# TLE5012_S2G1.net
KiCad netlist of a schematic drawn in Altium Designer
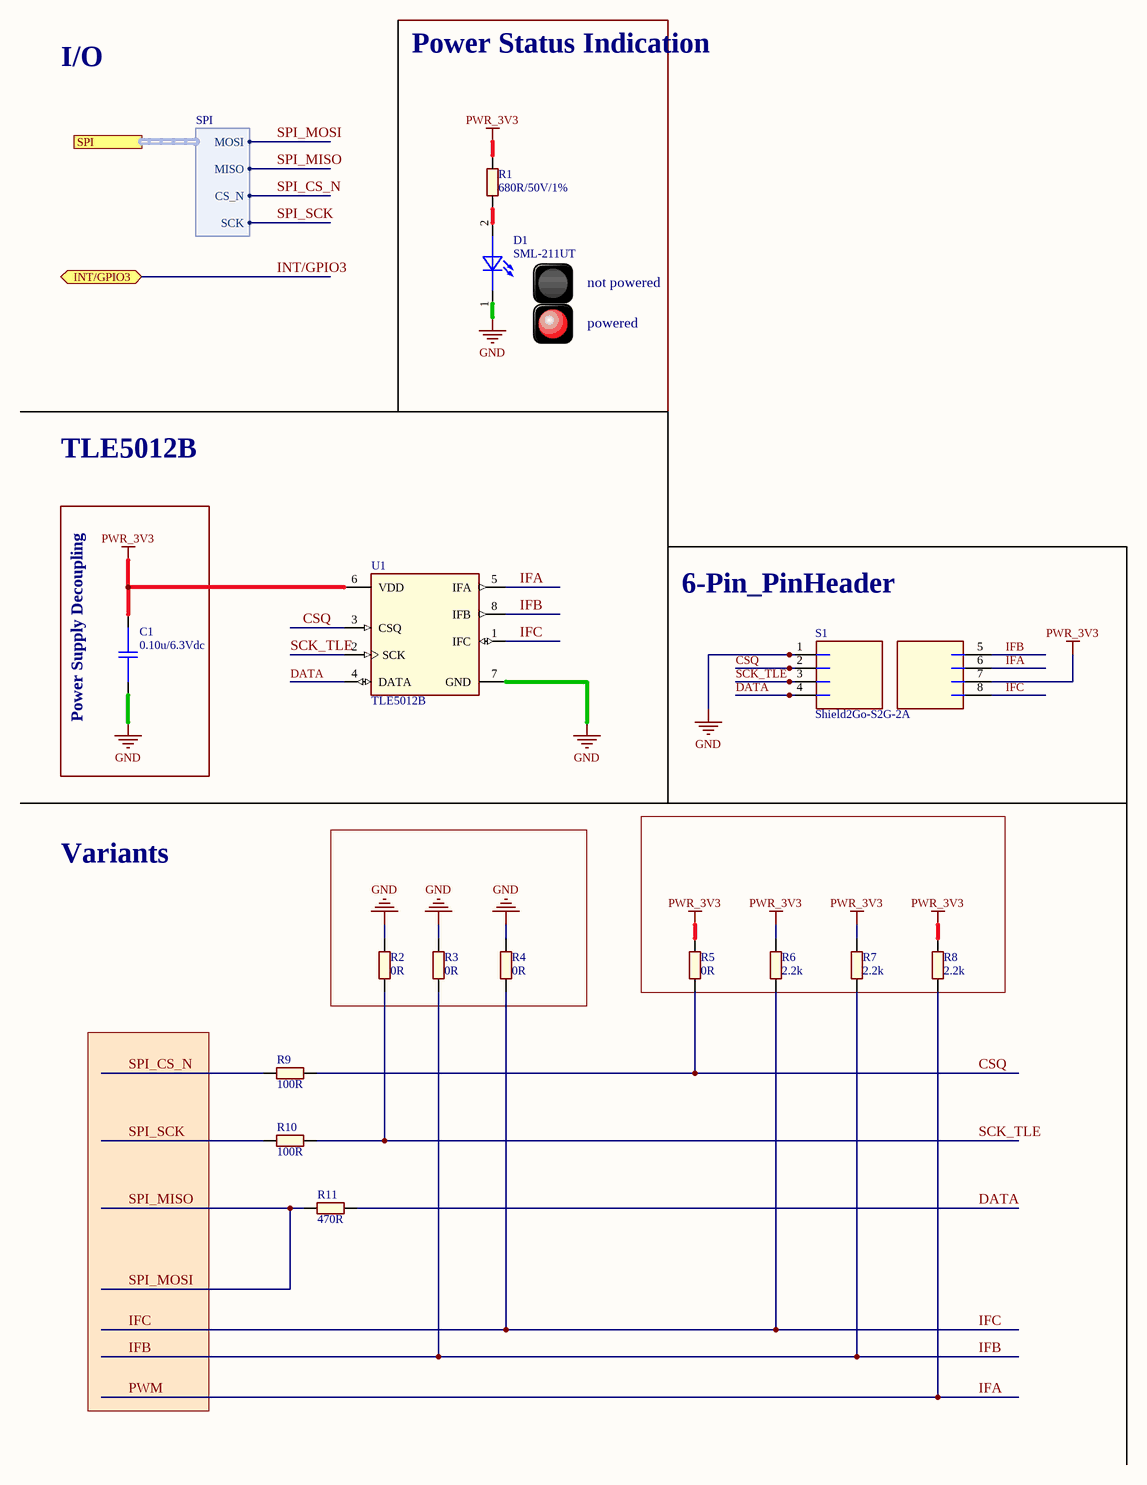
[diagram p0: TLE5012_S2G1.SchDoc]

(export (version "E")
  (design (tool "Eeschema 10.0.6"))
  (components
    (comp (ref "C1")
      (value "0.10u")
      (footprint "CAPC1005X55N-0")
      (description "GRM-Series General Purpose Monolithic Ceramic Capacitor")
      (fields
        (field (name "PARTNUMBER") "CAP01001501")
        (field (name "TYPE") "0.10u/6.3Vdc")
        (field (name "VOLTAGE") "6.3Vdc")
      )
      (libsource (lib "DB_External_Capacitor") (part "c_std_a"))
    )
    (comp (ref "D1")
      (value "SML-211UT")
      (footprint "LEDC2013X90N")
      (description "Mini-mold Chip LED, Red")
      (fields (field (name "PARTNUMBER") "DIO01300220") (field (name "VOLTAGE") "1.8V"))
      (libsource (lib "DB_External_Diode") (part "d_led_a"))
    )
    (comp (ref "R1")
      (value "680R")
      (footprint "RESC1005X03N")
      (description "680R/50V/1%")
      (fields
        (field (name "PARTNUMBER") "RES00000023")
        (field (name "TYPE") "680R/50V/1%")
        (field (name "POWER") "0.063W")
      )
      (libsource (lib "DB_External_Resistor") (part "resistor"))
    )
    (comp (ref "R2")
      (value "0R")
      (footprint "RESC2013X60N")
      (description "Automotive Grade Thick Film Chip Resistor")
      (fields (field (name "LEGACY PARTNUMBER") "RES00001814") (field (name "MANUFACTURER") "Yageo"))
      (libsource (lib "PCBLibraryData") (part "RES-SGL-STD-02P_00000006"))
    )
    (comp (ref "R3")
      (value "0R")
      (footprint "RESC2013X60N")
      (description "Automotive Grade Thick Film Chip Resistor")
      (fields (field (name "LEGACY PARTNUMBER") "RES00001814") (field (name "MANUFACTURER") "Yageo"))
      (libsource (lib "PCBLibraryData") (part "RES-SGL-STD-02P_00000006"))
    )
    (comp (ref "R4")
      (value "0R")
      (footprint "RESC2013X60N")
      (description "Automotive Grade Thick Film Chip Resistor")
      (fields (field (name "LEGACY PARTNUMBER") "RES00001814") (field (name "MANUFACTURER") "Yageo"))
      (libsource (lib "PCBLibraryData") (part "RES-SGL-STD-02P_00000006"))
    )
    (comp (ref "R5")
      (value "0R")
      (footprint "RESC2013X60N")
      (description "Automotive Grade Thick Film Chip Resistor")
      (fields (field (name "LEGACY PARTNUMBER") "RES00001814") (field (name "MANUFACTURER") "Yageo"))
      (libsource (lib "PCBLibraryData") (part "RES-SGL-STD-02P_00000006"))
    )
    (comp (ref "R6")
      (value "2.2k")
      (footprint "RESC2013X60N")
      (description "Automotive Grade Thick Film Chip Resistor")
      (fields (field (name "LEGACY PARTNUMBER") "RES00001814") (field (name "MANUFACTURER") "Yageo"))
      (libsource (lib "PCBLibraryData") (part "RES-SGL-STD-02P_00000006"))
    )
    (comp (ref "R7")
      (value "2.2k")
      (footprint "RESC2013X60N")
      (description "General Purpose Chip Resistor")
      (fields (field (name "LEGACY PARTNUMBER") "RES00000150") (field (name "MANUFACTURER") "Yageo"))
      (libsource (lib "PCBLibraryData") (part "RES-SGL-STD-02P_00000006"))
    )
    (comp (ref "R8")
      (value "2.2k")
      (footprint "RESC2013X60N")
      (description "General Purpose Chip Resistor")
      (fields (field (name "LEGACY PARTNUMBER") "RES00000150") (field (name "MANUFACTURER") "Yageo"))
      (libsource (lib "PCBLibraryData") (part "RES-SGL-STD-02P_00000006"))
    )
    (comp (ref "R9")
      (value "100R")
      (footprint "RESC2012X05N")
      (description "General Purpose Chip Resistor")
      (fields (field (name "LEGACY PARTNUMBER") "RES00000289") (field (name "MANUFACTURER") "Yageo"))
      (libsource (lib "") (part "RES-SGL-STD-02P_00000006_1"))
    )
    (comp (ref "R10")
      (value "100R")
      (footprint "RESC2012X05N")
      (description "General Purpose Chip Resistor")
      (fields (field (name "LEGACY PARTNUMBER") "RES00000289") (field (name "MANUFACTURER") "Yageo"))
      (libsource (lib "") (part "RES-SGL-STD-02P_00000006_1"))
    )
    (comp (ref "R11")
      (value "470R")
      (footprint "RESC2012X05N")
      (description "General Purpose Chip Resistor")
      (fields (field (name "LEGACY PARTNUMBER") "RES00000191") (field (name "MANUFACTURER") "Yageo"))
      (libsource (lib "") (part "RES-SGL-STD-02P_00000006_1"))
    )
    (comp (ref "S1")
      (value "Shield2Go-S2G-2A")
      (footprint "PIN_8_2R_4_A")
      (description "8 Pin Connector for Head of Shield2Go Boards")
      (fields (field (name "MANUFACTURER") "Infineon Technologies"))
      (libsource (lib "Shield2GoV1.1") (part "Shield2Go-S2G-2A"))
    )
    (comp (ref "U1")
      (value "TLE5012B")
      (footprint "SOIC127P600X175-8N-3")
      (description "GMR-Based Angle Sensor, SPI, IIF Interface")
      (fields (field (name "LEGACY PARTNUMBER") "IFX01400182") (field (name "MANUFACTURER") "Infineon"))
      (libsource (lib "PCBLibraryData") (part "TLE5012B"))
    )
  )
  (nets
    (net (code "2") (name "/CSQ") (class "Default")
      (node (ref "R5") (pin "1") (pinfunction "1_1") (pintype "passive"))
      (node (ref "R9") (pin "2") (pinfunction "2_2") (pintype "passive"))
      (node (ref "S1") (pin "2") (pinfunction "2_2") (pintype "passive"))
      (node (ref "U1") (pin "3") (pinfunction "CSQ_3") (pintype "input"))
    )
    (net (code "3") (name "/DATA") (class "Default")
      (node (ref "R11") (pin "2") (pinfunction "2_2") (pintype "passive"))
      (node (ref "S1") (pin "4") (pinfunction "4_4") (pintype "passive"))
      (node (ref "U1") (pin "4") (pinfunction "DATA_4") (pintype "bidirectional"))
    )
    (net (code "4") (name "/IFA") (class "Default")
      (node (ref "R8") (pin "1") (pinfunction "1_1") (pintype "passive"))
      (node (ref "S1") (pin "6") (pinfunction "6_6") (pintype "passive"))
      (node (ref "U1") (pin "5") (pinfunction "IFA_5") (pintype "output"))
    )
    (net (code "5") (name "/IFB") (class "Default")
      (node (ref "R3") (pin "1") (pinfunction "1_1") (pintype "passive"))
      (node (ref "R7") (pin "1") (pinfunction "1_1") (pintype "passive"))
      (node (ref "S1") (pin "5") (pinfunction "5_5") (pintype "passive"))
      (node (ref "U1") (pin "8") (pinfunction "IFB_8") (pintype "output"))
    )
    (net (code "6") (name "/IFC") (class "Default")
      (node (ref "R4") (pin "1") (pinfunction "1_1") (pintype "passive"))
      (node (ref "R6") (pin "1") (pinfunction "1_1") (pintype "passive"))
      (node (ref "S1") (pin "8") (pinfunction "8_8") (pintype "passive"))
      (node (ref "U1") (pin "1") (pinfunction "IFC_1") (pintype "bidirectional"))
    )
    (net (code "8") (name "/SCK_TLE") (class "Default")
      (node (ref "R10") (pin "2") (pinfunction "2_2") (pintype "passive"))
      (node (ref "R2") (pin "1") (pinfunction "1_1") (pintype "passive"))
      (node (ref "S1") (pin "3") (pinfunction "3_3") (pintype "passive"))
      (node (ref "U1") (pin "2") (pinfunction "SCK_2") (pintype "input"))
    )
    (net (code "9") (name "/SPI_CS_N") (class "Default")
      (node (ref "R9") (pin "1") (pinfunction "1_1") (pintype "passive"))
    )
    (net (code "10") (name "/SPI_MISO") (class "Default")
      (node (ref "R11") (pin "1") (pinfunction "1_1") (pintype "passive"))
    )
    (net (code "11") (name "/SPI_SCK") (class "Default")
      (node (ref "R10") (pin "1") (pinfunction "1_1") (pintype "passive"))
    )
    (net (code "13") (name "GND") (class "Default")
      (node (ref "C1") (pin "1") (pinfunction "1_1") (pintype "passive"))
      (node (ref "D1") (pin "1") (pinfunction "Cathode_1") (pintype "passive"))
      (node (ref "R2") (pin "2") (pinfunction "2_2") (pintype "passive"))
      (node (ref "R3") (pin "2") (pinfunction "2_2") (pintype "passive"))
      (node (ref "R4") (pin "2") (pinfunction "2_2") (pintype "passive"))
      (node (ref "S1") (pin "1") (pinfunction "1_1") (pintype "passive"))
      (node (ref "U1") (pin "7") (pinfunction "GND_7") (pintype "power_in"))
    )
    (net (code "14") (name "Net-(D1-Anode)") (class "Default")
      (node (ref "D1") (pin "2") (pinfunction "Anode_2") (pintype "passive"))
      (node (ref "R1") (pin "1") (pinfunction "1_1") (pintype "passive"))
    )
    (net (code "15") (name "PWR_3V3") (class "Default")
      (node (ref "C1") (pin "2") (pinfunction "2_2") (pintype "passive"))
      (node (ref "R1") (pin "2") (pinfunction "2_2") (pintype "passive"))
      (node (ref "R5") (pin "2") (pinfunction "2_2") (pintype "passive"))
      (node (ref "R6") (pin "2") (pinfunction "2_2") (pintype "passive"))
      (node (ref "R7") (pin "2") (pinfunction "2_2") (pintype "passive"))
      (node (ref "R8") (pin "2") (pinfunction "2_2") (pintype "passive"))
      (node (ref "S1") (pin "7") (pinfunction "7_7") (pintype "passive"))
      (node (ref "U1") (pin "6") (pinfunction "VDD_6") (pintype "power_in"))
    )
  )
)
